# STM32_Cheetah.net
KiCad netlist of a schematic drawn in Altium Designer
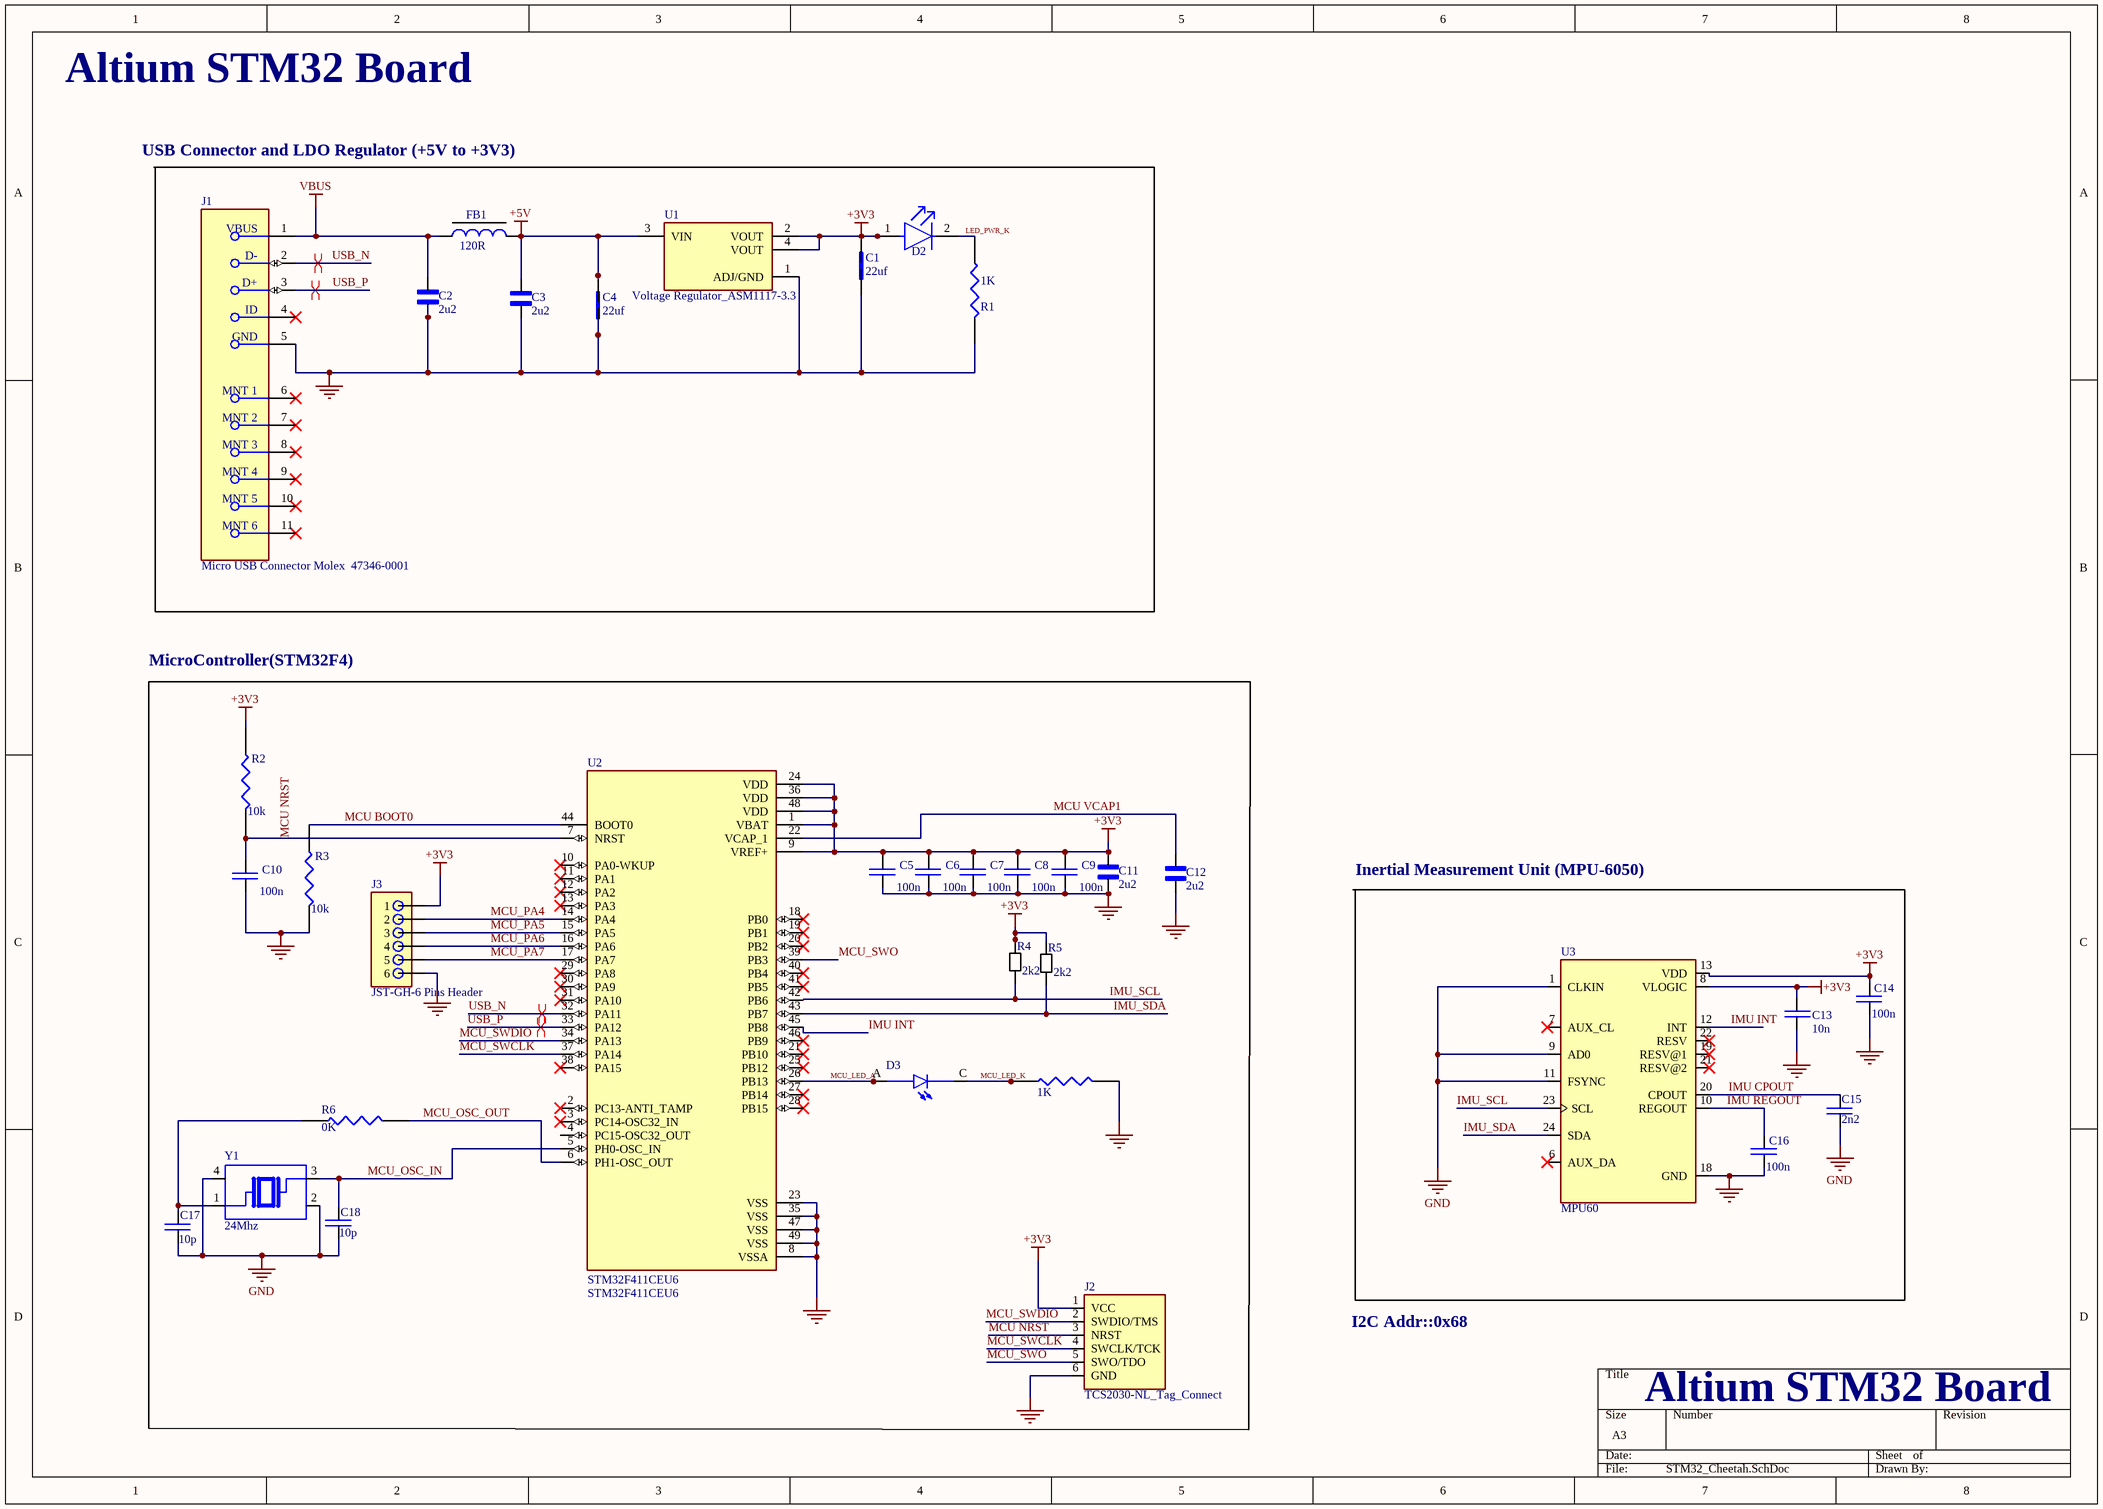
[diagram p0: STM32_Cheetah.SchDoc]

(export (version "E")
  (design (tool "Eeschema 10.0.6"))
  (components
    (comp (ref "1K")
      (value "Resistor_0402_Generic")
      (footprint "Resistor_0402_Generic")
      (description "130 kOhms Â±5% 0.1W, 1/10W Chip Resistor 0402 (1005 Metric) Automotive AEC-Q200 Thick Film")
      (libsource (lib "Integrated_Library_cheetah") (part "Resistor_0402_Generic"))
    )
    (comp (ref "C1")
      (value "22uf")
      (footprint "CAPC2012X140N")
      (description "COMMERCIAL CHIP STD JAPAN BULK - FN TAPE/REEL, 7 INCH PAPER TAPE")
      (libsource (lib "Integrated_Library_cheetah") (part "CAPC2012X140N-Capacitor0805"))
    )
    (comp (ref "C2")
      (value "2u2")
      (footprint "CAP_0603_Generic")
      (description "0.022 ÂµF Â±5% 16V Ceramic Capacitor X7R 0603 (1608 Metric)")
      (libsource (lib "Integrated_Library_cheetah") (part "CAP_0603_Generic"))
    )
    (comp (ref "C3")
      (value "2u2")
      (footprint "CAP_0603_Generic")
      (description "0.022 ÂµF Â±5% 16V Ceramic Capacitor X7R 0603 (1608 Metric)")
      (libsource (lib "Integrated_Library_cheetah") (part "CAP_0603_Generic"))
    )
    (comp (ref "C4")
      (value "22uf")
      (footprint "CAPC2012X140N")
      (description "COMMERCIAL CHIP STD JAPAN BULK - FN TAPE/REEL, 7 INCH PAPER TAPE")
      (libsource (lib "Integrated_Library_cheetah") (part "CAPC2012X140N-Capacitor0805"))
    )
    (comp (ref "C5")
      (value "100n")
      (footprint "CAP_0402_Generic")
      (description "0.022 ÂµF Â±5% 16V Ceramic Capacitor X7R 0603 (1608 Metric)")
      (libsource (lib "Integrated_Library_cheetah") (part "CAP_0402_Generic"))
    )
    (comp (ref "C6")
      (value "100n")
      (footprint "CAP_0402_Generic")
      (description "0.022 ÂµF Â±5% 16V Ceramic Capacitor X7R 0603 (1608 Metric)")
      (libsource (lib "Integrated_Library_cheetah") (part "CAP_0402_Generic"))
    )
    (comp (ref "C7")
      (value "100n")
      (footprint "CAP_0402_Generic")
      (description "0.022 ÂµF Â±5% 16V Ceramic Capacitor X7R 0603 (1608 Metric)")
      (libsource (lib "Integrated_Library_cheetah") (part "CAP_0402_Generic"))
    )
    (comp (ref "C8")
      (value "100n")
      (footprint "CAP_0402_Generic")
      (description "0.022 ÂµF Â±5% 16V Ceramic Capacitor X7R 0603 (1608 Metric)")
      (libsource (lib "Integrated_Library_cheetah") (part "CAP_0402_Generic"))
    )
    (comp (ref "C9")
      (value "100n")
      (footprint "CAP_0402_Generic")
      (description "0.022 ÂµF Â±5% 16V Ceramic Capacitor X7R 0603 (1608 Metric)")
      (libsource (lib "Integrated_Library_cheetah") (part "CAP_0402_Generic"))
    )
    (comp (ref "C10")
      (value "100n")
      (footprint "CAP_0402_Generic")
      (description "0.022 ÂµF Â±5% 16V Ceramic Capacitor X7R 0603 (1608 Metric)")
      (libsource (lib "Integrated_Library_cheetah") (part "CAP_0402_Generic"))
    )
    (comp (ref "C11")
      (value "2u2")
      (footprint "CAP_0603_Generic")
      (description "0.022 ÂµF Â±5% 16V Ceramic Capacitor X7R 0603 (1608 Metric)")
      (libsource (lib "Integrated_Library_cheetah") (part "CAP_0603_Generic"))
    )
    (comp (ref "C12")
      (value "2u2")
      (footprint "CAP_0603_Generic")
      (description "0.022 ÂµF Â±5% 16V Ceramic Capacitor X7R 0603 (1608 Metric)")
      (libsource (lib "Integrated_Library_cheetah") (part "CAP_0603_Generic"))
    )
    (comp (ref "C13")
      (value "10n")
      (footprint "CAP_0402_Generic")
      (description "0.022 ÂµF Â±5% 16V Ceramic Capacitor X7R 0603 (1608 Metric)")
      (libsource (lib "Integrated_Library_cheetah") (part "CAP_0402_Generic"))
    )
    (comp (ref "C14")
      (value "100n")
      (footprint "CAP_0402_Generic")
      (description "0.022 ÂµF Â±5% 16V Ceramic Capacitor X7R 0603 (1608 Metric)")
      (libsource (lib "Integrated_Library_cheetah") (part "CAP_0402_Generic"))
    )
    (comp (ref "C15")
      (value "2n2")
      (footprint "CAP_0402_Generic")
      (description "0.022 ÂµF Â±5% 16V Ceramic Capacitor X7R 0603 (1608 Metric)")
      (libsource (lib "Integrated_Library_cheetah") (part "CAP_0402_Generic"))
    )
    (comp (ref "C16")
      (value "100n")
      (footprint "CAP_0402_Generic")
      (description "0.022 ÂµF Â±5% 16V Ceramic Capacitor X7R 0603 (1608 Metric)")
      (libsource (lib "Integrated_Library_cheetah") (part "CAP_0402_Generic"))
    )
    (comp (ref "C17")
      (value "10p")
      (footprint "CAP_0402_Generic")
      (description "0.022 ÂµF Â±5% 16V Ceramic Capacitor X7R 0603 (1608 Metric)")
      (libsource (lib "Integrated_Library_cheetah") (part "CAP_0402_Generic"))
    )
    (comp (ref "C18")
      (value "10p")
      (footprint "CAP_0402_Generic")
      (description "0.022 ÂµF Â±5% 16V Ceramic Capacitor X7R 0603 (1608 Metric)")
      (libsource (lib "Integrated_Library_cheetah") (part "CAP_0402_Generic"))
    )
    (comp (ref "D2")
      (value "LED Green Wurth Elektronik 150080GS75000")
      (footprint "LED 0508 Green SMT")
      (description "WURTH ELEKTRONIK - 150080GS75000 - LED, Green, SMD, 0805, 30 mA, 3.2 V, 520 nm")
      (libsource (lib "Integrated_Library_cheetah") (part "LED Green Wurth Elektronik 150080GS75000"))
    )
    (comp (ref "D3")
      (value "0402 RED LED")
      (footprint "RED_LED_0402")
      (description "LED, PICOLED, Red, 621 nm, 1.8 V, 1 mA, 2.5 mcd")
      (libsource (lib "Integrated_Library_cheetah") (part "0402 RED LED"))
    )
    (comp (ref "FB1")
      (value "120R")
      (footprint "FB 0603")
      (description "Ferrite Bead SMD 0603")
      (libsource (lib "Integrated_Library_cheetah") (part "Ferrite Bead SMD 0603"))
    )
    (comp (ref "J1")
      (value "Micro USB Connector Molex  47346-0001")
      (footprint "Molex_0_MFG")
      (description "PN-473460001")
      (libsource (lib "Integrated_Library_cheetah") (part "Micro USB Connector Molex  47346-0001"))
    )
    (comp (ref "J2")
      (value "TCS2030-NL_Tag_Connect")
      (footprint "TCS_Tag-Connect")
      (description "Tag_Connect_CABLE ADAPTER 6 POS")
      (libsource (lib "Integrated_Library_cheetah") (part "TCS2030-NL_Tag_Connect"))
    )
    (comp (ref "J3")
      (value "JST-GH-6 Pins Header")
      (footprint "JST-GH 6 Pins Connector")
      (description "Connector Header Surface Mount 6 position 0.059 (1.50mm)")
      (libsource (lib "Integrated_Library_cheetah") (part "JST-GH-6 Pins Header"))
    )
    (comp (ref "R1")
      (value "1K")
      (footprint "Resistor_0402_Generic")
      (description "130 kOhms Â±5% 0.1W, 1/10W Chip Resistor 0402 (1005 Metric) Automotive AEC-Q200 Thick Film")
      (libsource (lib "Integrated_Library_cheetah") (part "Resistor_0402_Generic"))
    )
    (comp (ref "R2")
      (value "10k")
      (footprint "Resistor_0402_Generic")
      (description "130 kOhms Â±5% 0.1W, 1/10W Chip Resistor 0402 (1005 Metric) Automotive AEC-Q200 Thick Film")
      (libsource (lib "Integrated_Library_cheetah") (part "Resistor_0402_Generic"))
    )
    (comp (ref "R3")
      (value "10k")
      (footprint "Resistor_0402_Generic")
      (description "130 kOhms Â±5% 0.1W, 1/10W Chip Resistor 0402 (1005 Metric) Automotive AEC-Q200 Thick Film")
      (libsource (lib "Integrated_Library_cheetah") (part "Resistor_0402_Generic"))
    )
    (comp (ref "R4")
      (value "2k2")
      (footprint "Resistor_0402_Generic")
      (description "130 kOhms Â±5% 0.1W, 1/10W Chip Resistor 0402 (1005 Metric) Automotive AEC-Q200 Thick Film")
      (libsource (lib "") (part "Resistor_0402_Generic_1"))
    )
    (comp (ref "R5")
      (value "2k2")
      (footprint "Resistor_0402_Generic")
      (description "130 kOhms Â±5% 0.1W, 1/10W Chip Resistor 0402 (1005 Metric) Automotive AEC-Q200 Thick Film")
      (libsource (lib "") (part "Resistor_0402_Generic_1"))
    )
    (comp (ref "R6")
      (value "0K")
      (footprint "Resistor_0402_Generic")
      (description "130 kOhms Â±5% 0.1W, 1/10W Chip Resistor 0402 (1005 Metric) Automotive AEC-Q200 Thick Film")
      (libsource (lib "Integrated_Library_cheetah") (part "Resistor_0402_Generic"))
    )
    (comp (ref "U1")
      (value "Voltage Regulator_ASM1117-3.3")
      (footprint "Voltage_Regulator ASM1117-3.3")
      (description "1A LOW DROPOUT VOLTAGE REGULATOR SOT-223")
      (libsource (lib "Integrated_Library_cheetah") (part "Voltage Regulator_ASM1117-3.3"))
    )
    (comp (ref "U2")
      (value "STM32F411CEU6")
      (footprint "STM32F411CEU6")
      (libsource (lib "Integrated_Library_cheetah") (part "STM32F411CEU6"))
    )
    (comp (ref "U3")
      (value "MPU60")
      (footprint "MPU60")
      (description "MPU-6050 series Accelerometer, Gyroscope, 3 Axis Sensor Evaluation Board")
      (libsource (lib "Integrated_Library_cheetah") (part "MPU60"))
    )
    (comp (ref "Y1")
      (value "24Mhz")
      (footprint "TSX-Crystal Oscillator 24Mhz")
      (description "24MHz Â±10ppm Crystal 9pF 40 Ohms 4-SMD, No Lead")
      (libsource (lib "Integrated_Library_cheetah") (part "Crystal Socillator 24Mhz TSX-322524"))
    )
  )
  (nets
    (net (code "1") (name "+3V3") (class "Default")
      (node (ref "C1") (pin "2") (pinfunction "2_2") (pintype "passive"))
      (node (ref "C11") (pin "2") (pinfunction "2_2") (pintype "passive"))
      (node (ref "C13") (pin "1") (pinfunction "1_1") (pintype "passive"))
      (node (ref "C14") (pin "2") (pinfunction "2_2") (pintype "passive"))
      (node (ref "C5") (pin "2") (pinfunction "2_2") (pintype "passive"))
      (node (ref "C6") (pin "2") (pinfunction "2_2") (pintype "passive"))
      (node (ref "C7") (pin "2") (pinfunction "2_2") (pintype "passive"))
      (node (ref "C8") (pin "2") (pinfunction "2_2") (pintype "passive"))
      (node (ref "C9") (pin "2") (pinfunction "2_2") (pintype "passive"))
      (node (ref "D2") (pin "1") (pinfunction "A_1") (pintype "passive"))
      (node (ref "J2") (pin "1") (pinfunction "VCC_1") (pintype "passive"))
      (node (ref "J3") (pin "1") (pinfunction "1_1") (pintype "passive"))
      (node (ref "R2") (pin "2") (pinfunction "2_2") (pintype "passive"))
      (node (ref "R4") (pin "2") (pinfunction "2_2") (pintype "passive"))
      (node (ref "R5") (pin "2") (pinfunction "2_2") (pintype "passive"))
      (node (ref "U1") (pin "2") (pinfunction "VOUT_2") (pintype "passive"))
      (node (ref "U1") (pin "4") (pinfunction "VOUT_4") (pintype "passive"))
      (node (ref "U2") (pin "1") (pinfunction "VBAT_1") (pintype "power_in"))
      (node (ref "U2") (pin "24") (pinfunction "VDD_24") (pintype "power_in"))
      (node (ref "U2") (pin "36") (pinfunction "VDD_36") (pintype "power_in"))
      (node (ref "U2") (pin "48") (pinfunction "VDD_48") (pintype "power_in"))
      (node (ref "U2") (pin "9") (pinfunction "VREF+_9") (pintype "power_in"))
      (node (ref "U3") (pin "13") (pinfunction "VDD_13") (pintype "power_in"))
      (node (ref "U3") (pin "8") (pinfunction "VLOGIC_8") (pintype "passive"))
    )
    (net (code "2") (name "+5V") (class "Default")
      (node (ref "C3") (pin "2") (pinfunction "2_2") (pintype "passive"))
      (node (ref "C4") (pin "2") (pinfunction "2_2") (pintype "passive"))
      (node (ref "FB1") (pin "2") (pinfunction "2_2") (pintype "passive"))
      (node (ref "U1") (pin "3") (pinfunction "VIN_3") (pintype "passive"))
    )
    (net (code "3") (name "/IMU CPOUT") (class "Default")
      (node (ref "C15") (pin "2") (pinfunction "2_2") (pintype "passive"))
      (node (ref "U3") (pin "20") (pinfunction "CPOUT_20") (pintype "passive"))
    )
    (net (code "4") (name "/IMU INT") (class "Default")
      (node (ref "U2") (pin "45") (pinfunction "PB8_45") (pintype "bidirectional"))
      (node (ref "U3") (pin "12") (pinfunction "INT_12") (pintype "passive"))
    )
    (net (code "5") (name "/IMU REGOUT") (class "Default")
      (node (ref "C16") (pin "2") (pinfunction "2_2") (pintype "passive"))
      (node (ref "U3") (pin "10") (pinfunction "REGOUT_10") (pintype "passive"))
    )
    (net (code "6") (name "/IMU_SCL") (class "Default")
      (node (ref "R4") (pin "1") (pinfunction "1_1") (pintype "passive"))
      (node (ref "U2") (pin "42") (pinfunction "PB6_42") (pintype "bidirectional"))
      (node (ref "U3") (pin "23") (pinfunction "SCL_23") (pintype "passive"))
    )
    (net (code "7") (name "/IMU_SDA") (class "Default")
      (node (ref "R5") (pin "1") (pinfunction "1_1") (pintype "passive"))
      (node (ref "U2") (pin "43") (pinfunction "PB7_43") (pintype "bidirectional"))
      (node (ref "U3") (pin "24") (pinfunction "SDA_24") (pintype "passive"))
    )
    (net (code "8") (name "/LED_PWR_K") (class "Default")
      (node (ref "D2") (pin "2") (pinfunction "C_2") (pintype "passive"))
      (node (ref "R1") (pin "2") (pinfunction "2_2") (pintype "passive"))
    )
    (net (code "9") (name "/MCU BOOT0") (class "Default")
      (node (ref "R3") (pin "2") (pinfunction "2_2") (pintype "passive"))
      (node (ref "U2") (pin "44") (pinfunction "BOOT0_44") (pintype "passive"))
    )
    (net (code "10") (name "/MCU NRST") (class "Default")
      (node (ref "C10") (pin "2") (pinfunction "2_2") (pintype "passive"))
      (node (ref "J2") (pin "3") (pinfunction "NRST_3") (pintype "passive"))
      (node (ref "R2") (pin "1") (pinfunction "1_1") (pintype "passive"))
      (node (ref "U2") (pin "7") (pinfunction "NRST_7") (pintype "bidirectional"))
    )
    (net (code "11") (name "/MCU VCAP1") (class "Default")
      (node (ref "C12") (pin "2") (pinfunction "2_2") (pintype "passive"))
      (node (ref "U2") (pin "22") (pinfunction "VCAP_1_22") (pintype "power_in"))
    )
    (net (code "12") (name "/MCU_LED_A") (class "Default")
      (node (ref "D3") (pin "A") (pinfunction "A_A") (pintype "passive"))
      (node (ref "U2") (pin "26") (pinfunction "PB13_26") (pintype "bidirectional"))
    )
    (net (code "13") (name "/MCU_LED_K") (class "Default")
      (node (ref "1K") (pin "2") (pinfunction "2_2") (pintype "passive"))
      (node (ref "D3") (pin "C") (pinfunction "C_C") (pintype "passive"))
    )
    (net (code "14") (name "/MCU_OSC_IN") (class "Default")
      (node (ref "C18") (pin "2") (pinfunction "2_2") (pintype "passive"))
      (node (ref "U2") (pin "5") (pinfunction "PH0-OSC_IN_5") (pintype "bidirectional"))
      (node (ref "Y1") (pin "3") (pinfunction "3_3") (pintype "passive"))
    )
    (net (code "15") (name "/MCU_OSC_OUT") (class "Default")
      (node (ref "R6") (pin "1") (pinfunction "1_1") (pintype "passive"))
      (node (ref "U2") (pin "6") (pinfunction "PH1-OSC_OUT_6") (pintype "bidirectional"))
    )
    (net (code "16") (name "/MCU_PA4") (class "Default")
      (node (ref "J3") (pin "2") (pinfunction "2_2") (pintype "passive"))
      (node (ref "U2") (pin "14") (pinfunction "PA4_14") (pintype "bidirectional"))
    )
    (net (code "17") (name "/MCU_PA5") (class "Default")
      (node (ref "J3") (pin "3") (pinfunction "3_3") (pintype "passive"))
      (node (ref "U2") (pin "15") (pinfunction "PA5_15") (pintype "bidirectional"))
    )
    (net (code "18") (name "/MCU_PA6") (class "Default")
      (node (ref "J3") (pin "4") (pinfunction "4_4") (pintype "passive"))
      (node (ref "U2") (pin "16") (pinfunction "PA6_16") (pintype "bidirectional"))
    )
    (net (code "19") (name "/MCU_PA7") (class "Default")
      (node (ref "J3") (pin "5") (pinfunction "5_5") (pintype "passive"))
      (node (ref "U2") (pin "17") (pinfunction "PA7_17") (pintype "bidirectional"))
    )
    (net (code "20") (name "/MCU_SWCLK") (class "Default")
      (node (ref "J2") (pin "4") (pinfunction "SWCLK/TCK_4") (pintype "passive"))
      (node (ref "U2") (pin "37") (pinfunction "PA14_37") (pintype "bidirectional"))
    )
    (net (code "21") (name "/MCU_SWDIO") (class "Default")
      (node (ref "J2") (pin "2") (pinfunction "SWDIO/TMS_2") (pintype "passive"))
      (node (ref "U2") (pin "34") (pinfunction "PA13_34") (pintype "bidirectional"))
    )
    (net (code "22") (name "/MCU_SWO") (class "Default")
      (node (ref "J2") (pin "5") (pinfunction "SWO/TDO_5") (pintype "passive"))
      (node (ref "U2") (pin "39") (pinfunction "PB3_39") (pintype "bidirectional"))
    )
    (net (code "23") (name "/USB_N") (class "Default")
      (node (ref "J1") (pin "2") (pinfunction "D-_2") (pintype "bidirectional"))
      (node (ref "U2") (pin "32") (pinfunction "PA11_32") (pintype "bidirectional"))
    )
    (net (code "24") (name "/USB_P") (class "Default")
      (node (ref "J1") (pin "3") (pinfunction "D+_3") (pintype "bidirectional"))
      (node (ref "U2") (pin "33") (pinfunction "PA12_33") (pintype "bidirectional"))
    )
    (net (code "25") (name "GND") (class "Default")
      (node (ref "1K") (pin "1") (pinfunction "1_1") (pintype "passive"))
      (node (ref "C1") (pin "1") (pinfunction "1_1") (pintype "passive"))
      (node (ref "C10") (pin "1") (pinfunction "1_1") (pintype "passive"))
      (node (ref "C11") (pin "1") (pinfunction "1_1") (pintype "passive"))
      (node (ref "C12") (pin "1") (pinfunction "1_1") (pintype "passive"))
      (node (ref "C13") (pin "2") (pinfunction "2_2") (pintype "passive"))
      (node (ref "C14") (pin "1") (pinfunction "1_1") (pintype "passive"))
      (node (ref "C15") (pin "1") (pinfunction "1_1") (pintype "passive"))
      (node (ref "C16") (pin "1") (pinfunction "1_1") (pintype "passive"))
      (node (ref "C17") (pin "1") (pinfunction "1_1") (pintype "passive"))
      (node (ref "C18") (pin "1") (pinfunction "1_1") (pintype "passive"))
      (node (ref "C2") (pin "1") (pinfunction "1_1") (pintype "passive"))
      (node (ref "C3") (pin "1") (pinfunction "1_1") (pintype "passive"))
      (node (ref "C4") (pin "1") (pinfunction "1_1") (pintype "passive"))
      (node (ref "C5") (pin "1") (pinfunction "1_1") (pintype "passive"))
      (node (ref "C6") (pin "1") (pinfunction "1_1") (pintype "passive"))
      (node (ref "C7") (pin "1") (pinfunction "1_1") (pintype "passive"))
      (node (ref "C8") (pin "1") (pinfunction "1_1") (pintype "passive"))
      (node (ref "C9") (pin "1") (pinfunction "1_1") (pintype "passive"))
      (node (ref "J1") (pin "5") (pinfunction "GND_5") (pintype "power_in"))
      (node (ref "J2") (pin "6") (pinfunction "GND_6") (pintype "passive"))
      (node (ref "J3") (pin "6") (pinfunction "6_6") (pintype "passive"))
      (node (ref "R1") (pin "1") (pinfunction "1_1") (pintype "passive"))
      (node (ref "R3") (pin "1") (pinfunction "1_1") (pintype "passive"))
      (node (ref "U1") (pin "1") (pinfunction "ADJ/GND_1") (pintype "passive"))
      (node (ref "U2") (pin "23") (pinfunction "VSS_23") (pintype "power_in"))
      (node (ref "U2") (pin "35") (pinfunction "VSS_35") (pintype "power_in"))
      (node (ref "U2") (pin "47") (pinfunction "VSS_47") (pintype "power_in"))
      (node (ref "U2") (pin "49") (pinfunction "VSS_49") (pintype "power_in"))
      (node (ref "U2") (pin "8") (pinfunction "VSSA_8") (pintype "power_in"))
      (node (ref "U3") (pin "1") (pinfunction "CLKIN_1") (pintype "passive"))
      (node (ref "U3") (pin "11") (pinfunction "FSYNC_11") (pintype "passive"))
      (node (ref "U3") (pin "18") (pinfunction "GND_18") (pintype "power_in"))
      (node (ref "U3") (pin "9") (pinfunction "AD0_9") (pintype "passive"))
      (node (ref "Y1") (pin "2") (pinfunction "2_2") (pintype "passive"))
      (node (ref "Y1") (pin "4") (pinfunction "4_4") (pintype "passive"))
    )
    (net (code "26") (name "Net-(C17-Pad2)") (class "Default")
      (node (ref "C17") (pin "2") (pinfunction "2_2") (pintype "passive"))
      (node (ref "R6") (pin "2") (pinfunction "2_2") (pintype "passive"))
      (node (ref "Y1") (pin "1") (pinfunction "1_1") (pintype "passive"))
    )
    (net (code "27") (name "VBUS") (class "Default")
      (node (ref "C2") (pin "2") (pinfunction "2_2") (pintype "passive"))
      (node (ref "FB1") (pin "1") (pinfunction "1_1") (pintype "passive"))
      (node (ref "J1") (pin "1") (pinfunction "VBUS_1") (pintype "power_in"))
    )
    (net (code "28") (name "unconnected-(J1-ID-Pad4)") (class "Default")
      (node (ref "J1") (pin "4") (pinfunction "ID_4") (pintype "passive+no_connect"))
    )
    (net (code "29") (name "unconnected-(J1-MNT_1-Pad6)") (class "Default")
      (node (ref "J1") (pin "6") (pinfunction "MNT_1_6") (pintype "passive+no_connect"))
    )
    (net (code "30") (name "unconnected-(J1-MNT_2-Pad7)") (class "Default")
      (node (ref "J1") (pin "7") (pinfunction "MNT_2_7") (pintype "passive+no_connect"))
    )
    (net (code "31") (name "unconnected-(J1-MNT_3-Pad8)") (class "Default")
      (node (ref "J1") (pin "8") (pinfunction "MNT_3_8") (pintype "passive+no_connect"))
    )
    (net (code "32") (name "unconnected-(J1-MNT_4-Pad9)") (class "Default")
      (node (ref "J1") (pin "9") (pinfunction "MNT_4_9") (pintype "passive+no_connect"))
    )
    (net (code "33") (name "unconnected-(J1-MNT_5-Pad10)") (class "Default")
      (node (ref "J1") (pin "10") (pinfunction "MNT_5_10") (pintype "passive+no_connect"))
    )
    (net (code "34") (name "unconnected-(J1-MNT_6-Pad11)") (class "Default")
      (node (ref "J1") (pin "11") (pinfunction "MNT_6_11") (pintype "passive+no_connect"))
    )
    (net (code "35") (name "unconnected-(U2-PA0-WKUP-Pad10)") (class "Default")
      (node (ref "U2") (pin "10") (pinfunction "PA0-WKUP_10") (pintype "bidirectional+no_connect"))
    )
    (net (code "36") (name "unconnected-(U2-PA1-Pad11)") (class "Default")
      (node (ref "U2") (pin "11") (pinfunction "PA1_11") (pintype "bidirectional+no_connect"))
    )
    (net (code "37") (name "unconnected-(U2-PA2-Pad12)") (class "Default")
      (node (ref "U2") (pin "12") (pinfunction "PA2_12") (pintype "bidirectional+no_connect"))
    )
    (net (code "38") (name "unconnected-(U2-PA3-Pad13)") (class "Default")
      (node (ref "U2") (pin "13") (pinfunction "PA3_13") (pintype "bidirectional+no_connect"))
    )
    (net (code "39") (name "unconnected-(U2-PA8-Pad29)") (class "Default")
      (node (ref "U2") (pin "29") (pinfunction "PA8_29") (pintype "bidirectional+no_connect"))
    )
    (net (code "40") (name "unconnected-(U2-PA9-Pad30)") (class "Default")
      (node (ref "U2") (pin "30") (pinfunction "PA9_30") (pintype "bidirectional+no_connect"))
    )
    (net (code "41") (name "unconnected-(U2-PA10-Pad31)") (class "Default")
      (node (ref "U2") (pin "31") (pinfunction "PA10_31") (pintype "bidirectional+no_connect"))
    )
    (net (code "42") (name "unconnected-(U2-PA15-Pad38)") (class "Default")
      (node (ref "U2") (pin "38") (pinfunction "PA15_38") (pintype "bidirectional+no_connect"))
    )
    (net (code "43") (name "unconnected-(U2-PB0-Pad18)") (class "Default")
      (node (ref "U2") (pin "18") (pinfunction "PB0_18") (pintype "bidirectional+no_connect"))
    )
    (net (code "44") (name "unconnected-(U2-PB1-Pad19)") (class "Default")
      (node (ref "U2") (pin "19") (pinfunction "PB1_19") (pintype "bidirectional+no_connect"))
    )
    (net (code "45") (name "unconnected-(U2-PB2-Pad20)") (class "Default")
      (node (ref "U2") (pin "20") (pinfunction "PB2_20") (pintype "bidirectional+no_connect"))
    )
    (net (code "46") (name "unconnected-(U2-PB4-Pad40)") (class "Default")
      (node (ref "U2") (pin "40") (pinfunction "PB4_40") (pintype "bidirectional+no_connect"))
    )
    (net (code "47") (name "unconnected-(U2-PB5-Pad41)") (class "Default")
      (node (ref "U2") (pin "41") (pinfunction "PB5_41") (pintype "bidirectional+no_connect"))
    )
    (net (code "48") (name "unconnected-(U2-PB9-Pad46)") (class "Default")
      (node (ref "U2") (pin "46") (pinfunction "PB9_46") (pintype "bidirectional+no_connect"))
    )
    (net (code "49") (name "unconnected-(U2-PB10-Pad21)") (class "Default")
      (node (ref "U2") (pin "21") (pinfunction "PB10_21") (pintype "bidirectional+no_connect"))
    )
    (net (code "50") (name "unconnected-(U2-PB12-Pad25)") (class "Default")
      (node (ref "U2") (pin "25") (pinfunction "PB12_25") (pintype "bidirectional+no_connect"))
    )
    (net (code "51") (name "unconnected-(U2-PB14-Pad27)") (class "Default")
      (node (ref "U2") (pin "27") (pinfunction "PB14_27") (pintype "bidirectional+no_connect"))
    )
    (net (code "52") (name "unconnected-(U2-PB15-Pad28)") (class "Default")
      (node (ref "U2") (pin "28") (pinfunction "PB15_28") (pintype "bidirectional+no_connect"))
    )
    (net (code "53") (name "unconnected-(U2-PC13-ANTI_TAMP-Pad2)") (class "Default")
      (node (ref "U2") (pin "2") (pinfunction "PC13-ANTI_TAMP_2") (pintype "bidirectional+no_connect"))
    )
    (net (code "54") (name "unconnected-(U2-PC14-OSC32_IN-Pad3)") (class "Default")
      (node (ref "U2") (pin "3") (pinfunction "PC14-OSC32_IN_3") (pintype "bidirectional+no_connect"))
    )
    (net (code "55") (name "unconnected-(U2-PC15-OSC32_OUT-Pad4)") (class "Default")
      (node (ref "U2") (pin "4") (pinfunction "PC15-OSC32_OUT_4") (pintype "bidirectional"))
    )
    (net (code "56") (name "unconnected-(U3-AUX_CL-Pad7)") (class "Default")
      (node (ref "U3") (pin "7") (pinfunction "AUX_CL_7") (pintype "passive+no_connect"))
    )
    (net (code "57") (name "unconnected-(U3-AUX_DA-Pad6)") (class "Default")
      (node (ref "U3") (pin "6") (pinfunction "AUX_DA_6") (pintype "passive+no_connect"))
    )
    (net (code "58") (name "unconnected-(U3-RESV-Pad22)") (class "Default")
      (node (ref "U3") (pin "22") (pinfunction "RESV_22") (pintype "passive+no_connect"))
    )
    (net (code "59") (name "unconnected-(U3-RESV@1-Pad19)") (class "Default")
      (node (ref "U3") (pin "19") (pinfunction "RESV@1_19") (pintype "passive+no_connect"))
    )
    (net (code "60") (name "unconnected-(U3-RESV@2-Pad21)") (class "Default")
      (node (ref "U3") (pin "21") (pinfunction "RESV@2_21") (pintype "passive+no_connect"))
    )
  )
)
